# PSPS_AVNC_SRD_central-2020-10-23_FABRICA.net
KiCad netlist of a schematic drawn in EAGLE
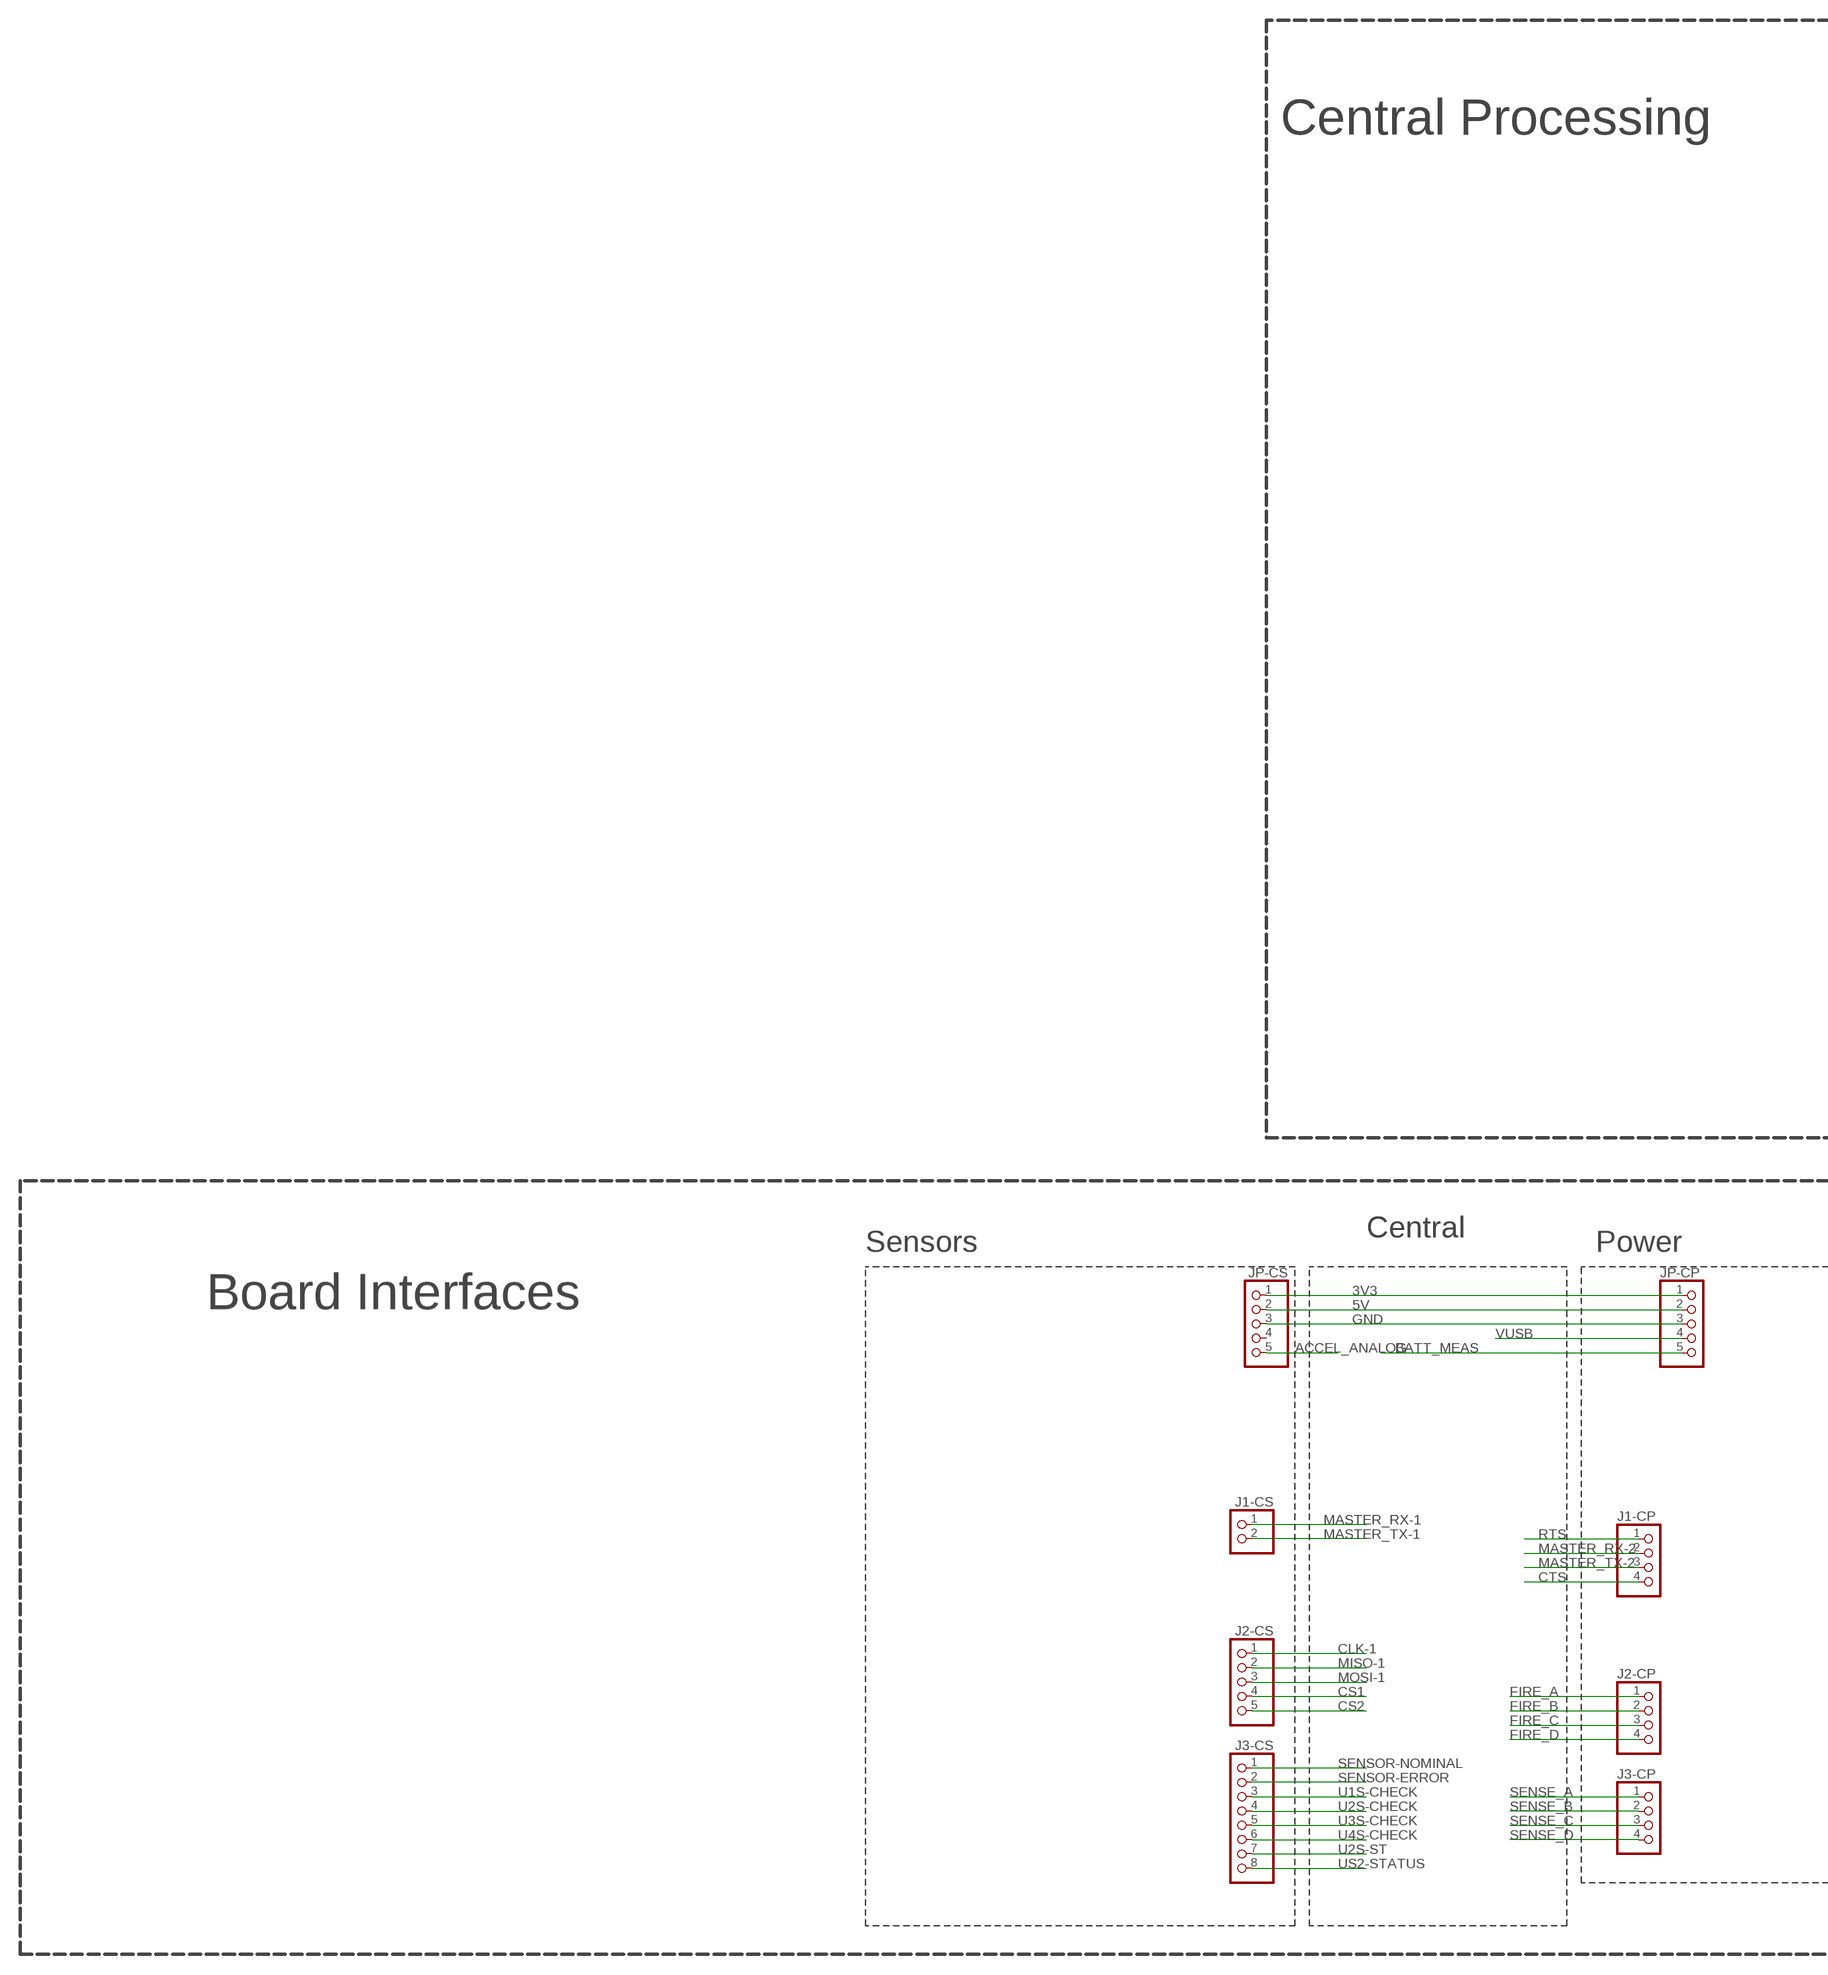
[diagram p0: schematic, sheet 1, part 1 of 2]
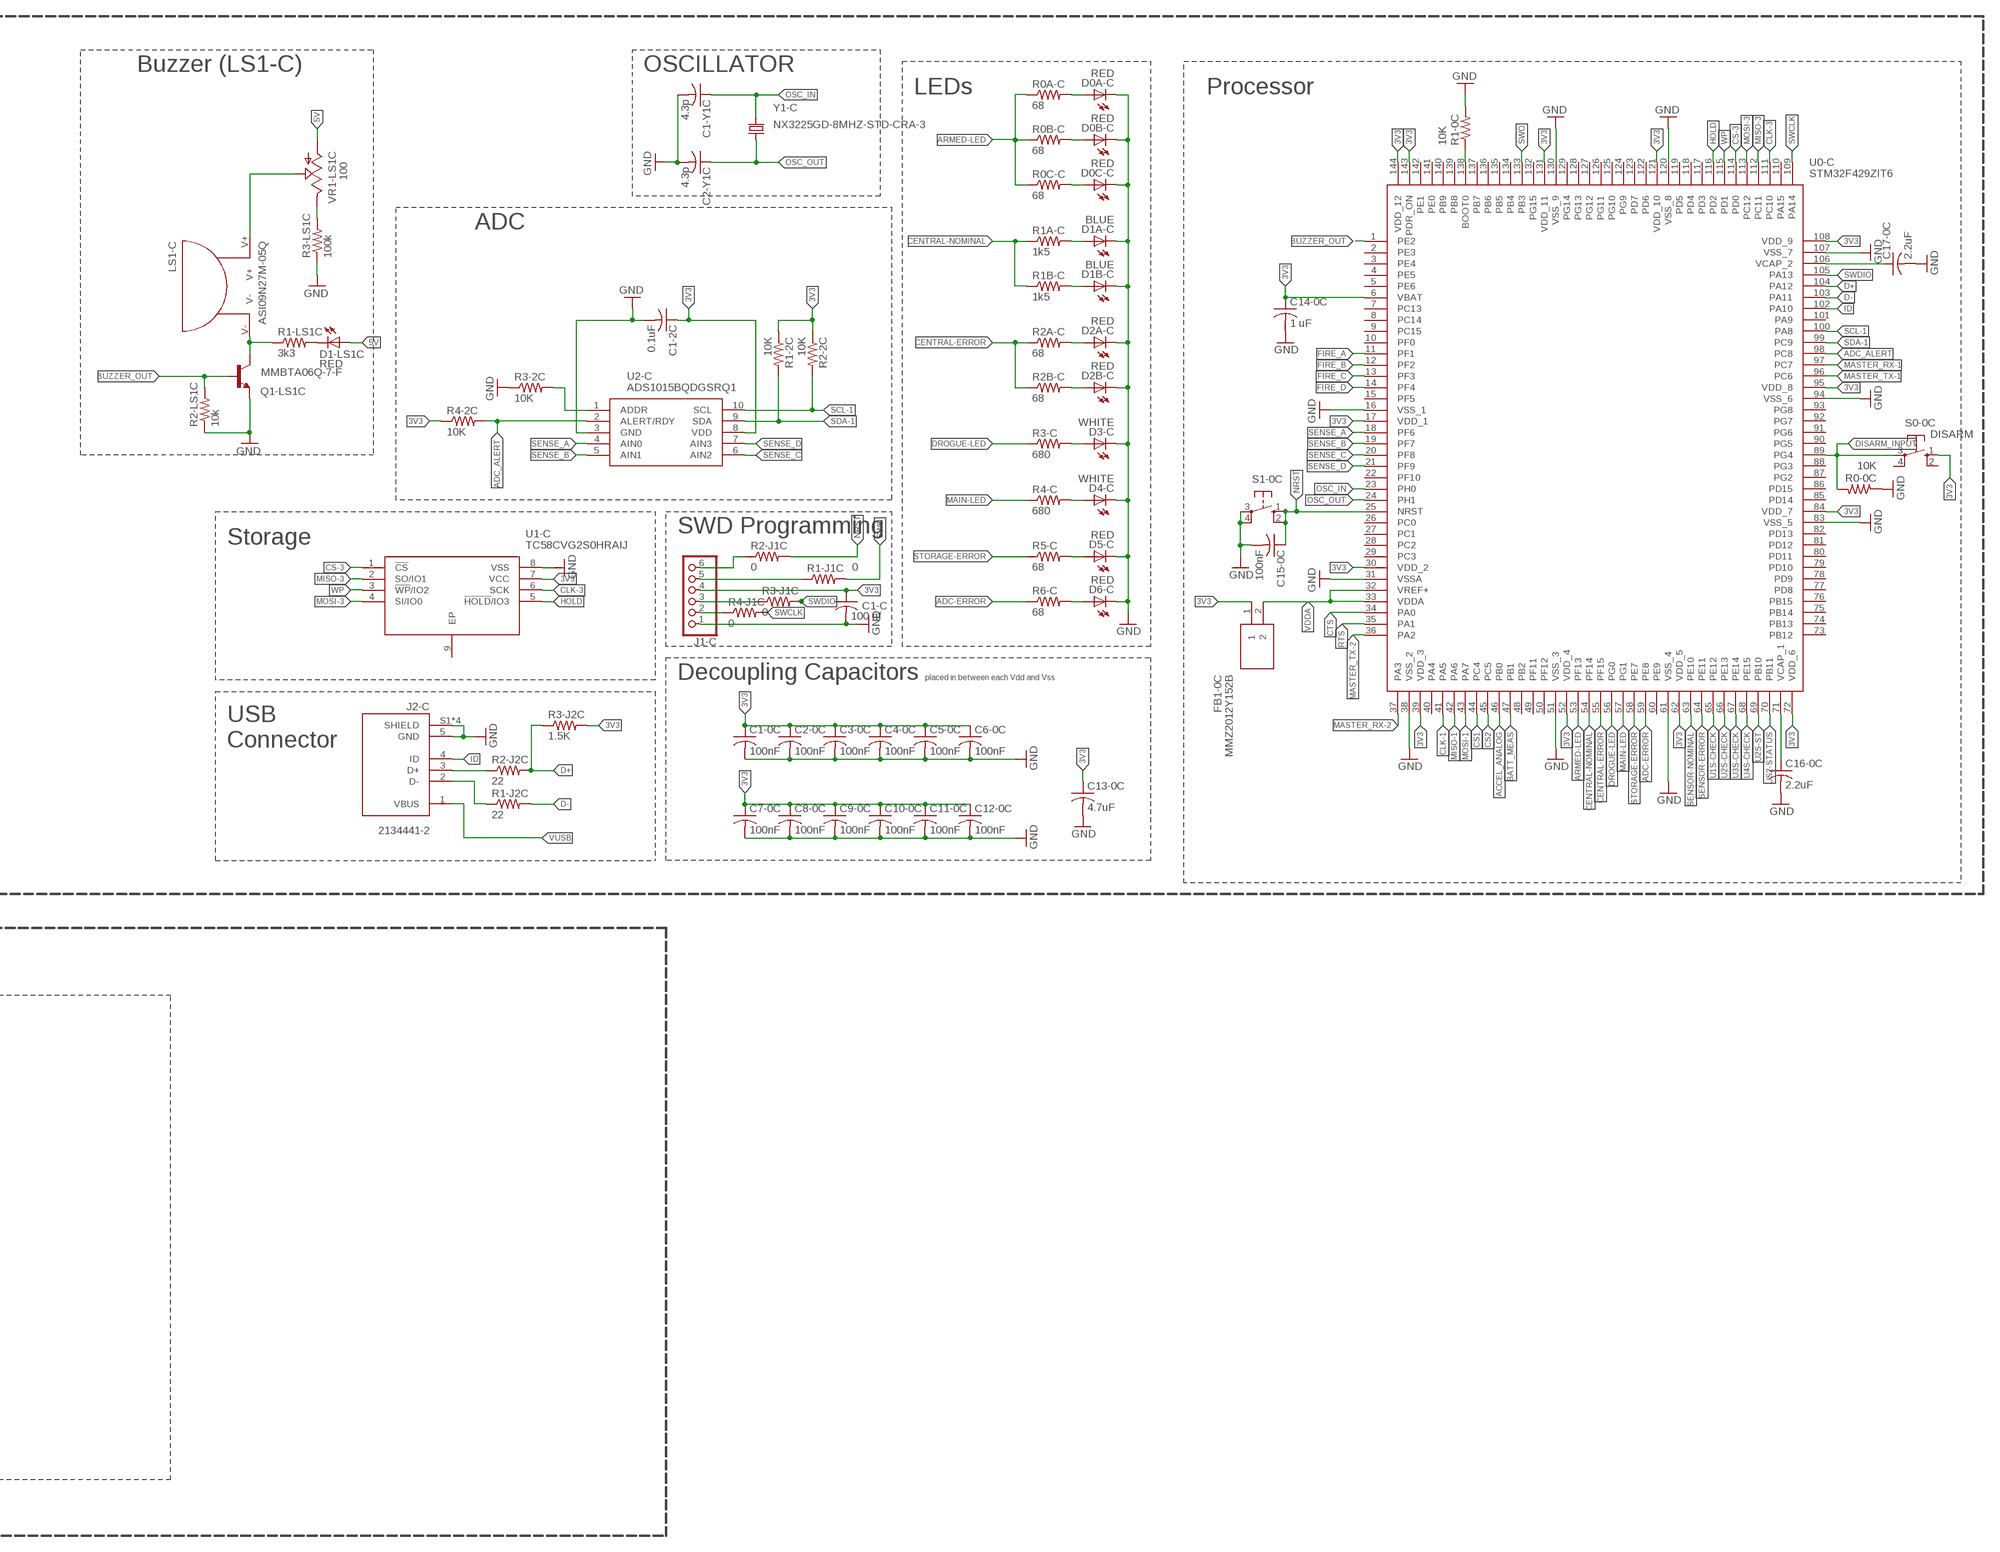
[diagram p1: schematic, sheet 1, part 2 of 2]

(export (version "E")
  (design (tool "Eeschema 10.0.6"))
  (components
    (comp (ref "C1-0C")
      (value "100nF")
      (footprint "eagle-import:C0805")
      (libsource (lib "eagle-import") (part "C-USC0805"))
    )
    (comp (ref "C1-2C")
      (value "0.1uF")
      (footprint "eagle-import:C0805")
      (libsource (lib "eagle-import") (part "C-USC0805"))
    )
    (comp (ref "C1-C")
      (value "100 nf")
      (footprint "eagle-import:C0805")
      (libsource (lib "eagle-import") (part "C-USC0805"))
    )
    (comp (ref "C1-Y1C")
      (value "4.3p")
      (footprint "eagle-import:C0805")
      (libsource (lib "eagle-import") (part "C-USC0805"))
    )
    (comp (ref "C2-0C")
      (value "100nF")
      (footprint "eagle-import:C0805")
      (libsource (lib "eagle-import") (part "C-USC0805"))
    )
    (comp (ref "C2-Y1C")
      (value "4.3p")
      (footprint "eagle-import:C0805")
      (libsource (lib "eagle-import") (part "C-USC0805"))
    )
    (comp (ref "C3-0C")
      (value "100nF")
      (footprint "eagle-import:C0805")
      (libsource (lib "eagle-import") (part "C-USC0805"))
    )
    (comp (ref "C4-0C")
      (value "100nF")
      (footprint "eagle-import:C0805")
      (libsource (lib "eagle-import") (part "C-USC0805"))
    )
    (comp (ref "C5-0C")
      (value "100nF")
      (footprint "eagle-import:C0805")
      (libsource (lib "eagle-import") (part "C-USC0805"))
    )
    (comp (ref "C6-0C")
      (value "100nF")
      (footprint "eagle-import:C0805")
      (libsource (lib "eagle-import") (part "C-USC0805"))
    )
    (comp (ref "C7-0C")
      (value "100nF")
      (footprint "eagle-import:C0805")
      (libsource (lib "eagle-import") (part "C-USC0805"))
    )
    (comp (ref "C8-0C")
      (value "100nF")
      (footprint "eagle-import:C0805")
      (libsource (lib "eagle-import") (part "C-USC0805"))
    )
    (comp (ref "C9-0C")
      (value "100nF")
      (footprint "eagle-import:C0805")
      (libsource (lib "eagle-import") (part "C-USC0805"))
    )
    (comp (ref "C10-0C")
      (value "100nF")
      (footprint "eagle-import:C0805")
      (libsource (lib "eagle-import") (part "C-USC0805"))
    )
    (comp (ref "C11-0C")
      (value "100nF")
      (footprint "eagle-import:C0805")
      (libsource (lib "eagle-import") (part "C-USC0805"))
    )
    (comp (ref "C12-0C")
      (value "100nF")
      (footprint "eagle-import:C0805")
      (libsource (lib "eagle-import") (part "C-USC0805"))
    )
    (comp (ref "C13-0C")
      (value "4.7uF")
      (footprint "eagle-import:C0805")
      (libsource (lib "eagle-import") (part "C-USC0805"))
    )
    (comp (ref "C14-0C")
      (value "1 uF")
      (footprint "eagle-import:C0805")
      (libsource (lib "eagle-import") (part "C-USC0805"))
    )
    (comp (ref "C15-0C")
      (value "100nF")
      (footprint "eagle-import:C0805")
      (libsource (lib "eagle-import") (part "C-USC0805"))
    )
    (comp (ref "C16-0C")
      (value "2.2uF")
      (footprint "eagle-import:C0805")
      (libsource (lib "eagle-import") (part "C-USC0805"))
    )
    (comp (ref "C17-0C")
      (value "2.2uF")
      (footprint "eagle-import:C0805")
      (libsource (lib "eagle-import") (part "C-USC0805"))
    )
    (comp (ref "D0A-C")
      (value "RED")
      (footprint "eagle-import:CHIPLED_0805")
      (libsource (lib "eagle-import") (part "LEDCHIPLED_0805"))
    )
    (comp (ref "D0B-C")
      (value "RED")
      (footprint "eagle-import:CHIPLED_0805")
      (libsource (lib "eagle-import") (part "LEDCHIPLED_0805"))
    )
    (comp (ref "D0C-C")
      (value "RED")
      (footprint "eagle-import:CHIPLED_0805")
      (libsource (lib "eagle-import") (part "LEDCHIPLED_0805"))
    )
    (comp (ref "D1-LS1C")
      (value "RED")
      (footprint "eagle-import:CHIPLED_0805")
      (libsource (lib "eagle-import") (part "LEDCHIPLED_0805"))
    )
    (comp (ref "D1A-C")
      (value "BLUE")
      (footprint "eagle-import:CHIPLED_0805")
      (libsource (lib "eagle-import") (part "LEDCHIPLED_0805"))
    )
    (comp (ref "D1B-C")
      (value "BLUE")
      (footprint "eagle-import:CHIPLED_0805")
      (libsource (lib "eagle-import") (part "LEDCHIPLED_0805"))
    )
    (comp (ref "D2A-C")
      (value "RED")
      (footprint "eagle-import:CHIPLED_0805")
      (libsource (lib "eagle-import") (part "LEDCHIPLED_0805"))
    )
    (comp (ref "D2B-C")
      (value "RED")
      (footprint "eagle-import:CHIPLED_0805")
      (libsource (lib "eagle-import") (part "LEDCHIPLED_0805"))
    )
    (comp (ref "D3-C")
      (value "WHITE")
      (footprint "eagle-import:CHIPLED_0805")
      (libsource (lib "eagle-import") (part "LEDCHIPLED_0805"))
    )
    (comp (ref "D4-C")
      (value "WHITE")
      (footprint "eagle-import:CHIPLED_0805")
      (libsource (lib "eagle-import") (part "LEDCHIPLED_0805"))
    )
    (comp (ref "D5-C")
      (value "RED")
      (footprint "eagle-import:CHIPLED_0805")
      (libsource (lib "eagle-import") (part "LEDCHIPLED_0805"))
    )
    (comp (ref "D6-C")
      (value "RED")
      (footprint "eagle-import:CHIPLED_0805")
      (libsource (lib "eagle-import") (part "LEDCHIPLED_0805"))
    )
    (comp (ref "FB1-0C")
      (value "MMZ2012Y152B")
      (footprint "eagle-import:BEADC2012X105N")
      (fields (field (name "MOUSER_PART_NUMBER") "810-MMZ2012Y152B"))
      (libsource (lib "eagle-import") (part "MMZ2012Y152B"))
    )
    (comp (ref "J1-C")
      (value "PINHD-1X6")
      (footprint "eagle-import:1X06")
      (libsource (lib "eagle-import") (part "PINHD-1X6"))
    )
    (comp (ref "J1-CP")
      (value "PINHD-1X4")
      (footprint "eagle-import:1X04")
      (libsource (lib "eagle-import") (part "PINHD-1X4"))
    )
    (comp (ref "J1-CS")
      (value "PINHD-1X2")
      (footprint "eagle-import:1X02")
      (libsource (lib "eagle-import") (part "PINHD-1X2"))
    )
    (comp (ref "J2-C")
      (value "2134441-2")
      (footprint "eagle-import:TE_2134441-2")
      (fields (field (name "DIGI-KEY_PART_NUMBER") "A118104CT-ND") (field (name "MF") "TE Connectivity"))
      (libsource (lib "eagle-import") (part "2134441-2"))
    )
    (comp (ref "J2-CP")
      (value "PINHD-1X4")
      (footprint "eagle-import:1X04")
      (libsource (lib "eagle-import") (part "PINHD-1X4"))
    )
    (comp (ref "J2-CS")
      (value "PINHD-1X5")
      (footprint "eagle-import:1X05")
      (libsource (lib "eagle-import") (part "PINHD-1X5"))
    )
    (comp (ref "J3-CP")
      (value "PINHD-1X4")
      (footprint "eagle-import:1X04")
      (libsource (lib "eagle-import") (part "PINHD-1X4"))
    )
    (comp (ref "J3-CS")
      (value "PINHD-1X8")
      (footprint "eagle-import:1X08")
      (libsource (lib "eagle-import") (part "PINHD-1X8"))
    )
    (comp (ref "JP-CP")
      (value "PINHD-1X5")
      (footprint "eagle-import:1X05")
      (libsource (lib "eagle-import") (part "PINHD-1X5"))
    )
    (comp (ref "JP-CS")
      (value "PINHD-1X5")
      (footprint "eagle-import:1X05")
      (libsource (lib "eagle-import") (part "PINHD-1X5"))
    )
    (comp (ref "LS1-C")
      (value "ASI09N27M-05Q")
      (footprint "eagle-import:ASI09N27M-05Q")
      (libsource (lib "eagle-import") (part "ASI09N27M-05Q"))
    )
    (comp (ref "Q1-LS1C")
      (value "MMBTA06Q-7-F")
      (footprint "eagle-import:SOT23")
      (libsource (lib "eagle-import") (part "NPN_TRANSISTOR"))
    )
    (comp (ref "R0-0C")
      (value "10K")
      (footprint "eagle-import:R0805")
      (libsource (lib "eagle-import") (part "R-US_R0805"))
    )
    (comp (ref "R0A-C")
      (value "68")
      (footprint "eagle-import:M0805")
      (libsource (lib "eagle-import") (part "R-US_M0805"))
    )
    (comp (ref "R0B-C")
      (value "68")
      (footprint "eagle-import:M0805")
      (libsource (lib "eagle-import") (part "R-US_M0805"))
    )
    (comp (ref "R0C-C")
      (value "68")
      (footprint "eagle-import:M0805")
      (libsource (lib "eagle-import") (part "R-US_M0805"))
    )
    (comp (ref "R1-0C")
      (value "10K")
      (footprint "eagle-import:R0805")
      (libsource (lib "eagle-import") (part "R-US_R0805"))
    )
    (comp (ref "R1-2C")
      (value "10K")
      (footprint "eagle-import:R0805")
      (libsource (lib "eagle-import") (part "R-US_R0805"))
    )
    (comp (ref "R1-J1C")
      (value "0")
      (footprint "eagle-import:M0805")
      (libsource (lib "eagle-import") (part "R-US_M0805"))
    )
    (comp (ref "R1-J2C")
      (value "22")
      (footprint "eagle-import:M0805")
      (libsource (lib "eagle-import") (part "R-US_M0805"))
    )
    (comp (ref "R1-LS1C")
      (value "3k3")
      (footprint "eagle-import:R0805")
      (libsource (lib "eagle-import") (part "resistor_348_R-US_R0805"))
    )
    (comp (ref "R1A-C")
      (value "1k5")
      (footprint "eagle-import:M0805")
      (libsource (lib "eagle-import") (part "R-US_M0805"))
    )
    (comp (ref "R1B-C")
      (value "1k5")
      (footprint "eagle-import:M0805")
      (libsource (lib "eagle-import") (part "R-US_M0805"))
    )
    (comp (ref "R2-2C")
      (value "10K")
      (footprint "eagle-import:R0805")
      (libsource (lib "eagle-import") (part "R-US_R0805"))
    )
    (comp (ref "R2-J1C")
      (value "0")
      (footprint "eagle-import:M0805")
      (libsource (lib "eagle-import") (part "R-US_M0805"))
    )
    (comp (ref "R2-J2C")
      (value "22")
      (footprint "eagle-import:M0805")
      (libsource (lib "eagle-import") (part "R-US_M0805"))
    )
    (comp (ref "R2-LS1C")
      (value "10k")
      (footprint "eagle-import:R0805")
      (libsource (lib "eagle-import") (part "resistor_348_R-US_R0805"))
    )
    (comp (ref "R2A-C")
      (value "68")
      (footprint "eagle-import:M0805")
      (libsource (lib "eagle-import") (part "R-US_M0805"))
    )
    (comp (ref "R2B-C")
      (value "68")
      (footprint "eagle-import:M0805")
      (libsource (lib "eagle-import") (part "R-US_M0805"))
    )
    (comp (ref "R3-2C")
      (value "10K")
      (footprint "eagle-import:R0805")
      (libsource (lib "eagle-import") (part "R-US_R0805"))
    )
    (comp (ref "R3-C")
      (value "680")
      (footprint "eagle-import:M0805")
      (libsource (lib "eagle-import") (part "R-US_M0805"))
    )
    (comp (ref "R3-J1C")
      (value "0")
      (footprint "eagle-import:M0805")
      (libsource (lib "eagle-import") (part "R-US_M0805"))
    )
    (comp (ref "R3-J2C")
      (value "1.5K")
      (footprint "eagle-import:M0805")
      (libsource (lib "eagle-import") (part "R-US_M0805"))
    )
    (comp (ref "R3-LS1C")
      (value "100k")
      (footprint "eagle-import:R0805")
      (libsource (lib "eagle-import") (part "resistor_348_R-US_R0805"))
    )
    (comp (ref "R4-2C")
      (value "10K")
      (footprint "eagle-import:R0805")
      (libsource (lib "eagle-import") (part "R-US_R0805"))
    )
    (comp (ref "R4-C")
      (value "680")
      (footprint "eagle-import:M0805")
      (libsource (lib "eagle-import") (part "R-US_M0805"))
    )
    (comp (ref "R4-J1C")
      (value "0")
      (footprint "eagle-import:M0805")
      (libsource (lib "eagle-import") (part "R-US_M0805"))
    )
    (comp (ref "R5-C")
      (value "68")
      (footprint "eagle-import:M0805")
      (libsource (lib "eagle-import") (part "R-US_M0805"))
    )
    (comp (ref "R6-C")
      (value "68")
      (footprint "eagle-import:M0805")
      (libsource (lib "eagle-import") (part "R-US_M0805"))
    )
    (comp (ref "S0-0C")
      (value "DISARM")
      (footprint "eagle-import:B3F-10XX")
      (fields (field (name "MPN") "B3F-1000"))
      (libsource (lib "eagle-import") (part "10-XX"))
    )
    (comp (ref "S1-0C")
      (value "10-XX")
      (footprint "eagle-import:B3F-10XX")
      (fields (field (name "MPN") "B3F-1000"))
      (libsource (lib "eagle-import") (part "10-XX"))
    )
    (comp (ref "U0-C")
      (value "STM32F429ZIT6")
      (footprint "eagle-import:QFP50P2200X2200X160-144N")
      (fields (field (name "MOUSER_PART_NUMBER") "511-STM32F429ZIT6"))
      (libsource (lib "eagle-import") (part "STM32F429ZIT6"))
    )
    (comp (ref "U1-C")
      (value "TC58CVG2S0HRAIJ")
      (footprint "eagle-import:SON127P800X600X80-9N")
      (fields (field (name "MOUSER_PART_NUMBER") "757-TC58CVG2S0HRAIJ"))
      (libsource (lib "eagle-import") (part "TC58CVG2S0HRAIJ"))
    )
    (comp (ref "U2-C")
      (value "ADS1015BQDGSRQ1")
      (footprint "eagle-import:SOP50P490X110-10N")
      (fields (field (name "MOUSER_PART_NUMBER") "595-ADS1015BQDGSRQ1"))
      (libsource (lib "eagle-import") (part "ADS1015BQDGSRQ1"))
    )
    (comp (ref "VR1-LS1C")
      (value "100")
      (footprint "eagle-import:LI10")
      (libsource (lib "eagle-import") (part "TRIM_US-LI10"))
    )
    (comp (ref "Y1-C")
      (value "NX3225GD-8MHZ-STD-CRA-3")
      (footprint "eagle-import:NX3225GD")
      (libsource (lib "eagle-import") (part "NX3225GD"))
    )
  )
  (nets
    (net (code "1") (name "3V3") (class "Default")
      (node (ref "C1-0C") (pin "1") (pinfunction "1_1") (pintype "passive"))
      (node (ref "C1-2C") (pin "1") (pinfunction "1_1") (pintype "passive"))
      (node (ref "C1-C") (pin "1") (pinfunction "1_1") (pintype "passive"))
      (node (ref "C10-0C") (pin "1") (pinfunction "1_1") (pintype "passive"))
      (node (ref "C11-0C") (pin "1") (pinfunction "1_1") (pintype "passive"))
      (node (ref "C12-0C") (pin "1") (pinfunction "1_1") (pintype "passive"))
      (node (ref "C13-0C") (pin "1") (pinfunction "1_1") (pintype "passive"))
      (node (ref "C14-0C") (pin "1") (pinfunction "1_1") (pintype "passive"))
      (node (ref "C2-0C") (pin "1") (pinfunction "1_1") (pintype "passive"))
      (node (ref "C3-0C") (pin "1") (pinfunction "1_1") (pintype "passive"))
      (node (ref "C4-0C") (pin "1") (pinfunction "1_1") (pintype "passive"))
      (node (ref "C5-0C") (pin "1") (pinfunction "1_1") (pintype "passive"))
      (node (ref "C6-0C") (pin "1") (pinfunction "1_1") (pintype "passive"))
      (node (ref "C7-0C") (pin "1") (pinfunction "1_1") (pintype "passive"))
      (node (ref "C8-0C") (pin "1") (pinfunction "1_1") (pintype "passive"))
      (node (ref "C9-0C") (pin "1") (pinfunction "1_1") (pintype "passive"))
      (node (ref "FB1-0C") (pin "1") (pinfunction "1_1") (pintype "bidirectional"))
      (node (ref "J1-C") (pin "4") (pinfunction "4_4") (pintype "passive"))
      (node (ref "JP-CP") (pin "1") (pinfunction "1_1") (pintype "passive"))
      (node (ref "JP-CS") (pin "1") (pinfunction "1_1") (pintype "passive"))
      (node (ref "R1-2C") (pin "1") (pinfunction "1_1") (pintype "passive"))
      (node (ref "R2-2C") (pin "1") (pinfunction "1_1") (pintype "passive"))
      (node (ref "R3-J2C") (pin "2") (pinfunction "2_2") (pintype "passive"))
      (node (ref "R4-2C") (pin "1") (pinfunction "1_1") (pintype "passive"))
      (node (ref "S0-0C") (pin "1") (pinfunction "S_1") (pintype "passive"))
      (node (ref "U0-C") (pin "108") (pinfunction "VDD_9_108") (pintype "power_in"))
      (node (ref "U0-C") (pin "121") (pinfunction "VDD_10_121") (pintype "power_in"))
      (node (ref "U0-C") (pin "131") (pinfunction "VDD_11_131") (pintype "power_in"))
      (node (ref "U0-C") (pin "143") (pinfunction "PDR_ON_143") (pintype "bidirectional"))
      (node (ref "U0-C") (pin "144") (pinfunction "VDD_12_144") (pintype "power_in"))
      (node (ref "U0-C") (pin "17") (pinfunction "VDD_1_17") (pintype "power_in"))
      (node (ref "U0-C") (pin "30") (pinfunction "VDD_2_30") (pintype "power_in"))
      (node (ref "U0-C") (pin "39") (pinfunction "VDD_3_39") (pintype "power_in"))
      (node (ref "U0-C") (pin "52") (pinfunction "VDD_4_52") (pintype "power_in"))
      (node (ref "U0-C") (pin "6") (pinfunction "VBAT_6") (pintype "bidirectional"))
      (node (ref "U0-C") (pin "62") (pinfunction "VDD_5_62") (pintype "power_in"))
      (node (ref "U0-C") (pin "72") (pinfunction "VDD_6_72") (pintype "power_in"))
      (node (ref "U0-C") (pin "84") (pinfunction "VDD_7_84") (pintype "power_in"))
      (node (ref "U0-C") (pin "95") (pinfunction "VDD_8_95") (pintype "power_in"))
      (node (ref "U1-C") (pin "7") (pinfunction "VCC_7") (pintype "bidirectional"))
      (node (ref "U2-C") (pin "8") (pinfunction "VDD_8") (pintype "bidirectional"))
    )
    (net (code "2") (name "5V") (class "Default")
      (node (ref "D1-LS1C") (pin "A") (pinfunction "A_A") (pintype "passive"))
      (node (ref "JP-CP") (pin "2") (pinfunction "2_2") (pintype "passive"))
      (node (ref "JP-CS") (pin "2") (pinfunction "2_2") (pintype "passive"))
      (node (ref "VR1-LS1C") (pin "A") (pinfunction "A_A") (pintype "passive"))
    )
    (net (code "3") (name "ACCEL_ANALOG") (class "Default")
      (node (ref "JP-CS") (pin "5") (pinfunction "5_5") (pintype "passive"))
      (node (ref "U0-C") (pin "46") (pinfunction "PB0_46") (pintype "bidirectional"))
    )
    (net (code "4") (name "ADC-ERROR") (class "Default")
      (node (ref "R6-C") (pin "1") (pinfunction "1_1") (pintype "passive"))
      (node (ref "U0-C") (pin "59") (pinfunction "PE8_59") (pintype "bidirectional"))
    )
    (net (code "5") (name "ADC_ALERT") (class "Default")
      (node (ref "R4-2C") (pin "2") (pinfunction "2_2") (pintype "passive"))
      (node (ref "U0-C") (pin "98") (pinfunction "PC8_98") (pintype "bidirectional"))
      (node (ref "U2-C") (pin "2") (pinfunction "ALERT/RDY_2") (pintype "bidirectional"))
    )
    (net (code "6") (name "ARMED-LED") (class "Default")
      (node (ref "R0A-C") (pin "1") (pinfunction "1_1") (pintype "passive"))
      (node (ref "R0B-C") (pin "1") (pinfunction "1_1") (pintype "passive"))
      (node (ref "R0C-C") (pin "1") (pinfunction "1_1") (pintype "passive"))
      (node (ref "U0-C") (pin "53") (pinfunction "PF13_53") (pintype "bidirectional"))
    )
    (net (code "7") (name "BATT_MEAS") (class "Default")
      (node (ref "JP-CP") (pin "5") (pinfunction "5_5") (pintype "passive"))
      (node (ref "U0-C") (pin "47") (pinfunction "PB1_47") (pintype "bidirectional"))
    )
    (net (code "8") (name "BUZZER_OUT") (class "Default")
      (node (ref "Q1-LS1C") (pin "1") (pinfunction "B_1") (pintype "passive"))
      (node (ref "R2-LS1C") (pin "2") (pinfunction "2_2") (pintype "passive"))
      (node (ref "U0-C") (pin "1") (pinfunction "PE2_1") (pintype "bidirectional"))
    )
    (net (code "9") (name "CENTRAL-ERROR") (class "Default")
      (node (ref "R2A-C") (pin "1") (pinfunction "1_1") (pintype "passive"))
      (node (ref "R2B-C") (pin "1") (pinfunction "1_1") (pintype "passive"))
      (node (ref "U0-C") (pin "55") (pinfunction "PF15_55") (pintype "bidirectional"))
    )
    (net (code "10") (name "CENTRAL-NOMINAL") (class "Default")
      (node (ref "R1A-C") (pin "1") (pinfunction "1_1") (pintype "passive"))
      (node (ref "R1B-C") (pin "1") (pinfunction "1_1") (pintype "passive"))
      (node (ref "U0-C") (pin "54") (pinfunction "PF14_54") (pintype "bidirectional"))
    )
    (net (code "11") (name "CLK-1") (class "Default")
      (node (ref "J2-CS") (pin "1") (pinfunction "1_1") (pintype "passive"))
      (node (ref "U0-C") (pin "41") (pinfunction "PA5_41") (pintype "bidirectional"))
    )
    (net (code "12") (name "CLK-3") (class "Default")
      (node (ref "U0-C") (pin "111") (pinfunction "PC10_111") (pintype "bidirectional"))
      (node (ref "U1-C") (pin "6") (pinfunction "SCK_6") (pintype "bidirectional"))
    )
    (net (code "13") (name "CS-3") (class "Default")
      (node (ref "U0-C") (pin "114") (pinfunction "PD0_114") (pintype "bidirectional"))
      (node (ref "U1-C") (pin "1") (pinfunction "~{CS}_1") (pintype "bidirectional"))
    )
    (net (code "14") (name "CS1") (class "Default")
      (node (ref "J2-CS") (pin "4") (pinfunction "4_4") (pintype "passive"))
      (node (ref "U0-C") (pin "44") (pinfunction "PC4_44") (pintype "bidirectional"))
    )
    (net (code "15") (name "CS2") (class "Default")
      (node (ref "J2-CS") (pin "5") (pinfunction "5_5") (pintype "passive"))
      (node (ref "U0-C") (pin "45") (pinfunction "PC5_45") (pintype "bidirectional"))
    )
    (net (code "16") (name "CTS") (class "Default")
      (node (ref "J1-CP") (pin "4") (pinfunction "4_4") (pintype "passive"))
      (node (ref "U0-C") (pin "34") (pinfunction "PA0_34") (pintype "bidirectional"))
    )
    (net (code "17") (name "D+") (class "Default")
      (node (ref "R2-J2C") (pin "2") (pinfunction "2_2") (pintype "passive"))
      (node (ref "R3-J2C") (pin "1") (pinfunction "1_1") (pintype "passive"))
      (node (ref "U0-C") (pin "104") (pinfunction "PA12_104") (pintype "bidirectional"))
    )
    (net (code "18") (name "D-") (class "Default")
      (node (ref "R1-J2C") (pin "2") (pinfunction "2_2") (pintype "passive"))
      (node (ref "U0-C") (pin "103") (pinfunction "PA11_103") (pintype "bidirectional"))
    )
    (net (code "19") (name "DISARM_INPUT") (class "Default")
      (node (ref "R0-0C") (pin "2") (pinfunction "2_2") (pintype "passive"))
      (node (ref "S0-0C") (pin "3") (pinfunction "P_3") (pintype "passive"))
      (node (ref "U0-C") (pin "89") (pinfunction "PG4_89") (pintype "bidirectional"))
    )
    (net (code "20") (name "DROGUE-LED") (class "Default")
      (node (ref "R3-C") (pin "1") (pinfunction "1_1") (pintype "passive"))
      (node (ref "U0-C") (pin "56") (pinfunction "PG0_56") (pintype "bidirectional"))
    )
    (net (code "21") (name "FIRE_A") (class "Default")
      (node (ref "J2-CP") (pin "1") (pinfunction "1_1") (pintype "passive"))
      (node (ref "U0-C") (pin "11") (pinfunction "PF1_11") (pintype "bidirectional"))
    )
    (net (code "22") (name "FIRE_B") (class "Default")
      (node (ref "J2-CP") (pin "2") (pinfunction "2_2") (pintype "passive"))
      (node (ref "U0-C") (pin "12") (pinfunction "PF2_12") (pintype "bidirectional"))
    )
    (net (code "23") (name "FIRE_C") (class "Default")
      (node (ref "J2-CP") (pin "3") (pinfunction "3_3") (pintype "passive"))
      (node (ref "U0-C") (pin "13") (pinfunction "PF3_13") (pintype "bidirectional"))
    )
    (net (code "24") (name "FIRE_D") (class "Default")
      (node (ref "J2-CP") (pin "4") (pinfunction "4_4") (pintype "passive"))
      (node (ref "U0-C") (pin "14") (pinfunction "PF4_14") (pintype "bidirectional"))
    )
    (net (code "25") (name "GND") (class "Default")
      (node (ref "C1-0C") (pin "2") (pinfunction "2_2") (pintype "passive"))
      (node (ref "C1-2C") (pin "2") (pinfunction "2_2") (pintype "passive"))
      (node (ref "C1-C") (pin "2") (pinfunction "2_2") (pintype "passive"))
      (node (ref "C1-Y1C") (pin "2") (pinfunction "2_2") (pintype "passive"))
      (node (ref "C10-0C") (pin "2") (pinfunction "2_2") (pintype "passive"))
      (node (ref "C11-0C") (pin "2") (pinfunction "2_2") (pintype "passive"))
      (node (ref "C12-0C") (pin "2") (pinfunction "2_2") (pintype "passive"))
      (node (ref "C13-0C") (pin "2") (pinfunction "2_2") (pintype "passive"))
      (node (ref "C14-0C") (pin "2") (pinfunction "2_2") (pintype "passive"))
      (node (ref "C15-0C") (pin "2") (pinfunction "2_2") (pintype "passive"))
      (node (ref "C16-0C") (pin "2") (pinfunction "2_2") (pintype "passive"))
      (node (ref "C17-0C") (pin "2") (pinfunction "2_2") (pintype "passive"))
      (node (ref "C2-0C") (pin "2") (pinfunction "2_2") (pintype "passive"))
      (node (ref "C2-Y1C") (pin "2") (pinfunction "2_2") (pintype "passive"))
      (node (ref "C3-0C") (pin "2") (pinfunction "2_2") (pintype "passive"))
      (node (ref "C4-0C") (pin "2") (pinfunction "2_2") (pintype "passive"))
      (node (ref "C5-0C") (pin "2") (pinfunction "2_2") (pintype "passive"))
      (node (ref "C6-0C") (pin "2") (pinfunction "2_2") (pintype "passive"))
      (node (ref "C7-0C") (pin "2") (pinfunction "2_2") (pintype "passive"))
      (node (ref "C8-0C") (pin "2") (pinfunction "2_2") (pintype "passive"))
      (node (ref "C9-0C") (pin "2") (pinfunction "2_2") (pintype "passive"))
      (node (ref "D0A-C") (pin "C") (pinfunction "C_C") (pintype "passive"))
      (node (ref "D0B-C") (pin "C") (pinfunction "C_C") (pintype "passive"))
      (node (ref "D0C-C") (pin "C") (pinfunction "C_C") (pintype "passive"))
      (node (ref "D1A-C") (pin "C") (pinfunction "C_C") (pintype "passive"))
      (node (ref "D1B-C") (pin "C") (pinfunction "C_C") (pintype "passive"))
      (node (ref "D2A-C") (pin "C") (pinfunction "C_C") (pintype "passive"))
      (node (ref "D2B-C") (pin "C") (pinfunction "C_C") (pintype "passive"))
      (node (ref "D3-C") (pin "C") (pinfunction "C_C") (pintype "passive"))
      (node (ref "D4-C") (pin "C") (pinfunction "C_C") (pintype "passive"))
      (node (ref "D5-C") (pin "C") (pinfunction "C_C") (pintype "passive"))
      (node (ref "D6-C") (pin "C") (pinfunction "C_C") (pintype "passive"))
      (node (ref "J1-C") (pin "1") (pinfunction "1_1") (pintype "passive"))
      (node (ref "J2-C") (pin "5") (pinfunction "GND_5") (pintype "power_in"))
      (node (ref "J2-C") (pin "S1") (pinfunction "SHIELD_S1") (pintype "power_in"))
      (node (ref "J2-C") (pin "S2") (pinfunction "SHIELD_S2") (pintype "power_in"))
      (node (ref "J2-C") (pin "S3") (pinfunction "SHIELD_S3") (pintype "power_in"))
      (node (ref "J2-C") (pin "S4") (pinfunction "SHIELD_S4") (pintype "power_in"))
      (node (ref "JP-CP") (pin "3") (pinfunction "3_3") (pintype "passive"))
      (node (ref "JP-CS") (pin "3") (pinfunction "3_3") (pintype "passive"))
      (node (ref "Q1-LS1C") (pin "3") (pinfunction "E_3") (pintype "passive"))
      (node (ref "R0-0C") (pin "1") (pinfunction "1_1") (pintype "passive"))
      (node (ref "R1-0C") (pin "2") (pinfunction "2_2") (pintype "passive"))
      (node (ref "R2-LS1C") (pin "1") (pinfunction "1_1") (pintype "passive"))
      (node (ref "R3-2C") (pin "1") (pinfunction "1_1") (pintype "passive"))
      (node (ref "R3-LS1C") (pin "1") (pinfunction "1_1") (pintype "passive"))
      (node (ref "S1-0C") (pin "3") (pinfunction "P_3") (pintype "passive"))
      (node (ref "S1-0C") (pin "4") (pinfunction "P1_4") (pintype "passive"))
      (node (ref "U0-C") (pin "107") (pinfunction "VSS_7_107") (pintype "power_in"))
      (node (ref "U0-C") (pin "120") (pinfunction "VSS_8_120") (pintype "power_in"))
      (node (ref "U0-C") (pin "130") (pinfunction "VSS_9_130") (pintype "power_in"))
      (node (ref "U0-C") (pin "16") (pinfunction "VSS_1_16") (pintype "power_in"))
      (node (ref "U0-C") (pin "31") (pinfunction "VSSA_31") (pintype "power_in"))
      (node (ref "U0-C") (pin "38") (pinfunction "VSS_2_38") (pintype "power_in"))
      (node (ref "U0-C") (pin "51") (pinfunction "VSS_3_51") (pintype "power_in"))
      (node (ref "U0-C") (pin "61") (pinfunction "VSS_4_61") (pintype "power_in"))
      (node (ref "U0-C") (pin "83") (pinfunction "VSS_5_83") (pintype "power_in"))
      (node (ref "U0-C") (pin "94") (pinfunction "VSS_6_94") (pintype "power_in"))
      (node (ref "U1-C") (pin "8") (pinfunction "VSS_8") (pintype "bidirectional"))
      (node (ref "U2-C") (pin "3") (pinfunction "GND_3") (pintype "bidirectional"))
    )
    (net (code "26") (name "HOLD") (class "Default")
      (node (ref "U0-C") (pin "116") (pinfunction "PD2_116") (pintype "bidirectional"))
      (node (ref "U1-C") (pin "5") (pinfunction "~{HOLD}/IO3_5") (pintype "bidirectional"))
    )
    (net (code "27") (name "ID") (class "Default")
      (node (ref "J2-C") (pin "4") (pinfunction "ID_4") (pintype "bidirectional"))
      (node (ref "U0-C") (pin "102") (pinfunction "PA10_102") (pintype "bidirectional"))
    )
    (net (code "28") (name "MAIN-LED") (class "Default")
      (node (ref "R4-C") (pin "1") (pinfunction "1_1") (pintype "passive"))
      (node (ref "U0-C") (pin "57") (pinfunction "PG1_57") (pintype "bidirectional"))
    )
    (net (code "29") (name "MASTER_RX-1") (class "Default")
      (node (ref "J1-CS") (pin "1") (pinfunction "1_1") (pintype "passive"))
      (node (ref "U0-C") (pin "97") (pinfunction "PC7_97") (pintype "bidirectional"))
    )
    (net (code "30") (name "MASTER_RX-2") (class "Default")
      (node (ref "J1-CP") (pin "2") (pinfunction "2_2") (pintype "passive"))
      (node (ref "U0-C") (pin "37") (pinfunction "PA3_37") (pintype "bidirectional"))
    )
    (net (code "31") (name "MASTER_TX-1") (class "Default")
      (node (ref "J1-CS") (pin "2") (pinfunction "2_2") (pintype "passive"))
      (node (ref "U0-C") (pin "96") (pinfunction "PC6_96") (pintype "bidirectional"))
    )
    (net (code "32") (name "MASTER_TX-2") (class "Default")
      (node (ref "J1-CP") (pin "3") (pinfunction "3_3") (pintype "passive"))
      (node (ref "U0-C") (pin "36") (pinfunction "PA2_36") (pintype "bidirectional"))
    )
    (net (code "33") (name "MISO-1") (class "Default")
      (node (ref "J2-CS") (pin "2") (pinfunction "2_2") (pintype "passive"))
      (node (ref "U0-C") (pin "42") (pinfunction "PA6_42") (pintype "bidirectional"))
    )
    (net (code "34") (name "MISO-3") (class "Default")
      (node (ref "U0-C") (pin "112") (pinfunction "PC11_112") (pintype "bidirectional"))
      (node (ref "U1-C") (pin "2") (pinfunction "SO/IO1_2") (pintype "bidirectional"))
    )
    (net (code "35") (name "MOSI-1") (class "Default")
      (node (ref "J2-CS") (pin "3") (pinfunction "3_3") (pintype "passive"))
      (node (ref "U0-C") (pin "43") (pinfunction "PA7_43") (pintype "bidirectional"))
    )
    (net (code "36") (name "MOSI-3") (class "Default")
      (node (ref "U0-C") (pin "113") (pinfunction "PC12_113") (pintype "bidirectional"))
      (node (ref "U1-C") (pin "4") (pinfunction "SI/IO0_4") (pintype "bidirectional"))
    )
    (net (code "37") (name "NRST") (class "Default")
      (node (ref "C15-0C") (pin "1") (pinfunction "1_1") (pintype "passive"))
      (node (ref "R2-J1C") (pin "2") (pinfunction "2_2") (pintype "passive"))
      (node (ref "S1-0C") (pin "1") (pinfunction "S_1") (pintype "passive"))
      (node (ref "S1-0C") (pin "2") (pinfunction "S1_2") (pintype "passive"))
      (node (ref "U0-C") (pin "25") (pinfunction "NRST_25") (pintype "input"))
    )
    (net (code "38") (name "Net-(D0A-C-PadA)") (class "Default")
      (node (ref "D0A-C") (pin "A") (pinfunction "A_A") (pintype "passive"))
      (node (ref "R0A-C") (pin "2") (pinfunction "2_2") (pintype "passive"))
    )
    (net (code "39") (name "Net-(D0B-C-PadA)") (class "Default")
      (node (ref "D0B-C") (pin "A") (pinfunction "A_A") (pintype "passive"))
      (node (ref "R0B-C") (pin "2") (pinfunction "2_2") (pintype "passive"))
    )
    (net (code "40") (name "Net-(D0C-C-PadA)") (class "Default")
      (node (ref "D0C-C") (pin "A") (pinfunction "A_A") (pintype "passive"))
      (node (ref "R0C-C") (pin "2") (pinfunction "2_2") (pintype "passive"))
    )
    (net (code "41") (name "Net-(D1-LS1C-PadC)") (class "Default")
      (node (ref "D1-LS1C") (pin "C") (pinfunction "C_C") (pintype "passive"))
      (node (ref "R1-LS1C") (pin "2") (pinfunction "2_2") (pintype "passive"))
    )
    (net (code "42") (name "Net-(D1A-C-PadA)") (class "Default")
      (node (ref "D1A-C") (pin "A") (pinfunction "A_A") (pintype "passive"))
      (node (ref "R1A-C") (pin "2") (pinfunction "2_2") (pintype "passive"))
    )
    (net (code "43") (name "Net-(D1B-C-PadA)") (class "Default")
      (node (ref "D1B-C") (pin "A") (pinfunction "A_A") (pintype "passive"))
      (node (ref "R1B-C") (pin "2") (pinfunction "2_2") (pintype "passive"))
    )
    (net (code "44") (name "Net-(D2A-C-PadA)") (class "Default")
      (node (ref "D2A-C") (pin "A") (pinfunction "A_A") (pintype "passive"))
      (node (ref "R2A-C") (pin "2") (pinfunction "2_2") (pintype "passive"))
    )
    (net (code "45") (name "Net-(D2B-C-PadA)") (class "Default")
      (node (ref "D2B-C") (pin "A") (pinfunction "A_A") (pintype "passive"))
      (node (ref "R2B-C") (pin "2") (pinfunction "2_2") (pintype "passive"))
    )
    (net (code "46") (name "Net-(D3-C-PadA)") (class "Default")
      (node (ref "D3-C") (pin "A") (pinfunction "A_A") (pintype "passive"))
      (node (ref "R3-C") (pin "2") (pinfunction "2_2") (pintype "passive"))
    )
    (net (code "47") (name "Net-(D4-C-PadA)") (class "Default")
      (node (ref "D4-C") (pin "A") (pinfunction "A_A") (pintype "passive"))
      (node (ref "R4-C") (pin "2") (pinfunction "2_2") (pintype "passive"))
    )
    (net (code "48") (name "Net-(D5-C-PadA)") (class "Default")
      (node (ref "D5-C") (pin "A") (pinfunction "A_A") (pintype "passive"))
      (node (ref "R5-C") (pin "2") (pinfunction "2_2") (pintype "passive"))
    )
    (net (code "49") (name "Net-(D6-C-PadA)") (class "Default")
      (node (ref "D6-C") (pin "A") (pinfunction "A_A") (pintype "passive"))
      (node (ref "R6-C") (pin "2") (pinfunction "2_2") (pintype "passive"))
    )
    (net (code "50") (name "Net-(J1-C-Pad2)") (class "Default")
      (node (ref "J1-C") (pin "2") (pinfunction "2_2") (pintype "passive"))
      (node (ref "R4-J1C") (pin "1") (pinfunction "1_1") (pintype "passive"))
    )
    (net (code "51") (name "Net-(J1-C-Pad3)") (class "Default")
      (node (ref "J1-C") (pin "3") (pinfunction "3_3") (pintype "passive"))
      (node (ref "R3-J1C") (pin "1") (pinfunction "1_1") (pintype "passive"))
    )
    (net (code "52") (name "Net-(J1-C-Pad5)") (class "Default")
      (node (ref "J1-C") (pin "5") (pinfunction "5_5") (pintype "passive"))
      (node (ref "R1-J1C") (pin "1") (pinfunction "1_1") (pintype "passive"))
    )
    (net (code "53") (name "Net-(J1-C-Pad6)") (class "Default")
      (node (ref "J1-C") (pin "6") (pinfunction "6_6") (pintype "passive"))
      (node (ref "R2-J1C") (pin "1") (pinfunction "1_1") (pintype "passive"))
    )
    (net (code "54") (name "Net-(J2-C-D+)") (class "Default")
      (node (ref "J2-C") (pin "3") (pinfunction "D+_3") (pintype "bidirectional"))
      (node (ref "R2-J2C") (pin "1") (pinfunction "1_1") (pintype "passive"))
    )
    (net (code "55") (name "Net-(J2-C-D-)") (class "Default")
      (node (ref "J2-C") (pin "2") (pinfunction "D-_2") (pintype "bidirectional"))
      (node (ref "R1-J2C") (pin "1") (pinfunction "1_1") (pintype "passive"))
    )
    (net (code "56") (name "Net-(LS1-C-PadV+)") (class "Default")
      (node (ref "LS1-C") (pin "V+") (pinfunction "V+_V+") (pintype "bidirectional"))
      (node (ref "VR1-LS1C") (pin "S") (pinfunction "S_S") (pintype "passive"))
    )
    (net (code "57") (name "Net-(Q1-LS1C-C)") (class "Default")
      (node (ref "LS1-C") (pin "V-") (pinfunction "V-_V-") (pintype "bidirectional"))
      (node (ref "Q1-LS1C") (pin "2") (pinfunction "C_2") (pintype "passive"))
      (node (ref "R1-LS1C") (pin "1") (pinfunction "1_1") (pintype "passive"))
    )
    (net (code "58") (name "Net-(R3-LS1C-Pad2)") (class "Default")
      (node (ref "R3-LS1C") (pin "2") (pinfunction "2_2") (pintype "passive"))
      (node (ref "VR1-LS1C") (pin "E") (pinfunction "E_E") (pintype "passive"))
    )
    (net (code "59") (name "Net-(U0-C-BOOT0)") (class "Default")
      (node (ref "R1-0C") (pin "1") (pinfunction "1_1") (pintype "passive"))
      (node (ref "U0-C") (pin "138") (pinfunction "BOOT0_138") (pintype "bidirectional"))
    )
    (net (code "60") (name "Net-(U0-C-VCAP_1)") (class "Default")
      (node (ref "C16-0C") (pin "1") (pinfunction "1_1") (pintype "passive"))
      (node (ref "U0-C") (pin "71") (pinfunction "VCAP_1_71") (pintype "bidirectional"))
    )
    (net (code "61") (name "Net-(U0-C-VCAP_2)") (class "Default")
      (node (ref "C17-0C") (pin "1") (pinfunction "1_1") (pintype "passive"))
      (node (ref "U0-C") (pin "106") (pinfunction "VCAP_2_106") (pintype "bidirectional"))
    )
    (net (code "62") (name "Net-(U2-C-ADDR)") (class "Default")
      (node (ref "R3-2C") (pin "2") (pinfunction "2_2") (pintype "passive"))
      (node (ref "U2-C") (pin "1") (pinfunction "ADDR_1") (pintype "bidirectional"))
    )
    (net (code "63") (name "OSC_IN") (class "Default")
      (node (ref "C1-Y1C") (pin "1") (pinfunction "1_1") (pintype "passive"))
      (node (ref "U0-C") (pin "23") (pinfunction "PH0_23") (pintype "bidirectional"))
      (node (ref "Y1-C") (pin "P$2") (pinfunction "2_P$2") (pintype "passive"))
    )
    (net (code "64") (name "OSC_OUT") (class "Default")
      (node (ref "C2-Y1C") (pin "1") (pinfunction "1_1") (pintype "passive"))
      (node (ref "U0-C") (pin "24") (pinfunction "PH1_24") (pintype "bidirectional"))
      (node (ref "Y1-C") (pin "P$1") (pinfunction "1_P$1") (pintype "passive"))
    )
    (net (code "65") (name "RTS") (class "Default")
      (node (ref "J1-CP") (pin "1") (pinfunction "1_1") (pintype "passive"))
      (node (ref "U0-C") (pin "35") (pinfunction "PA1_35") (pintype "bidirectional"))
    )
    (net (code "66") (name "SCL-1") (class "Default")
      (node (ref "R2-2C") (pin "2") (pinfunction "2_2") (pintype "passive"))
      (node (ref "U0-C") (pin "100") (pinfunction "PA8_100") (pintype "bidirectional"))
      (node (ref "U2-C") (pin "10") (pinfunction "SCL_10") (pintype "bidirectional"))
    )
    (net (code "67") (name "SDA-1") (class "Default")
      (node (ref "R1-2C") (pin "2") (pinfunction "2_2") (pintype "passive"))
      (node (ref "U0-C") (pin "99") (pinfunction "PC9_99") (pintype "bidirectional"))
      (node (ref "U2-C") (pin "9") (pinfunction "SDA_9") (pintype "bidirectional"))
    )
    (net (code "68") (name "SENSE_A") (class "Default")
      (node (ref "J3-CP") (pin "1") (pinfunction "1_1") (pintype "passive"))
      (node (ref "U0-C") (pin "18") (pinfunction "PF6_18") (pintype "bidirectional"))
      (node (ref "U2-C") (pin "4") (pinfunction "AIN0_4") (pintype "bidirectional"))
    )
    (net (code "69") (name "SENSE_B") (class "Default")
      (node (ref "J3-CP") (pin "2") (pinfunction "2_2") (pintype "passive"))
      (node (ref "U0-C") (pin "19") (pinfunction "PF7_19") (pintype "bidirectional"))
      (node (ref "U2-C") (pin "5") (pinfunction "AIN1_5") (pintype "bidirectional"))
    )
    (net (code "70") (name "SENSE_C") (class "Default")
      (node (ref "J3-CP") (pin "3") (pinfunction "3_3") (pintype "passive"))
      (node (ref "U0-C") (pin "20") (pinfunction "PF8_20") (pintype "bidirectional"))
      (node (ref "U2-C") (pin "6") (pinfunction "AIN2_6") (pintype "bidirectional"))
    )
    (net (code "71") (name "SENSE_D") (class "Default")
      (node (ref "J3-CP") (pin "4") (pinfunction "4_4") (pintype "passive"))
      (node (ref "U0-C") (pin "21") (pinfunction "PF9_21") (pintype "bidirectional"))
      (node (ref "U2-C") (pin "7") (pinfunction "AIN3_7") (pintype "bidirectional"))
    )
    (net (code "72") (name "SENSOR-ERROR") (class "Default")
      (node (ref "J3-CS") (pin "2") (pinfunction "2_2") (pintype "passive"))
      (node (ref "U0-C") (pin "64") (pinfunction "PE11_64") (pintype "bidirectional"))
    )
    (net (code "73") (name "SENSOR-NOMINAL") (class "Default")
      (node (ref "J3-CS") (pin "1") (pinfunction "1_1") (pintype "passive"))
      (node (ref "U0-C") (pin "63") (pinfunction "PE10_63") (pintype "bidirectional"))
    )
    (net (code "74") (name "STORAGE-ERROR") (class "Default")
      (node (ref "R5-C") (pin "1") (pinfunction "1_1") (pintype "passive"))
      (node (ref "U0-C") (pin "58") (pinfunction "PE7_58") (pintype "bidirectional"))
    )
    (net (code "75") (name "SWCLK") (class "Default")
      (node (ref "R4-J1C") (pin "2") (pinfunction "2_2") (pintype "passive"))
      (node (ref "U0-C") (pin "109") (pinfunction "PA14_109") (pintype "bidirectional"))
    )
    (net (code "76") (name "SWDIO") (class "Default")
      (node (ref "R3-J1C") (pin "2") (pinfunction "2_2") (pintype "passive"))
      (node (ref "U0-C") (pin "105") (pinfunction "PA13_105") (pintype "bidirectional"))
    )
    (net (code "77") (name "SWO") (class "Default")
      (node (ref "R1-J1C") (pin "2") (pinfunction "2_2") (pintype "passive"))
      (node (ref "U0-C") (pin "133") (pinfunction "PB3_133") (pintype "bidirectional"))
    )
    (net (code "78") (name "U1S-CHECK") (class "Default")
      (node (ref "J3-CS") (pin "3") (pinfunction "3_3") (pintype "passive"))
      (node (ref "U0-C") (pin "65") (pinfunction "PE12_65") (pintype "bidirectional"))
    )
    (net (code "79") (name "U2S-CHECK") (class "Default")
      (node (ref "J3-CS") (pin "4") (pinfunction "4_4") (pintype "passive"))
      (node (ref "U0-C") (pin "66") (pinfunction "PE13_66") (pintype "bidirectional"))
    )
    (net (code "80") (name "U2S-ST") (class "Default")
      (node (ref "J3-CS") (pin "7") (pinfunction "7_7") (pintype "passive"))
      (node (ref "U0-C") (pin "69") (pinfunction "PB10_69") (pintype "bidirectional"))
    )
    (net (code "81") (name "U3S-CHECK") (class "Default")
      (node (ref "J3-CS") (pin "5") (pinfunction "5_5") (pintype "passive"))
      (node (ref "U0-C") (pin "67") (pinfunction "PE14_67") (pintype "bidirectional"))
    )
    (net (code "82") (name "U4S-CHECK") (class "Default")
      (node (ref "J3-CS") (pin "6") (pinfunction "6_6") (pintype "passive"))
      (node (ref "U0-C") (pin "68") (pinfunction "PE15_68") (pintype "bidirectional"))
    )
    (net (code "83") (name "US2-STATUS") (class "Default")
      (node (ref "J3-CS") (pin "8") (pinfunction "8_8") (pintype "passive"))
      (node (ref "U0-C") (pin "70") (pinfunction "PB11_70") (pintype "bidirectional"))
    )
    (net (code "84") (name "VDDA") (class "Default")
      (node (ref "FB1-0C") (pin "2") (pinfunction "2_2") (pintype "bidirectional"))
      (node (ref "U0-C") (pin "32") (pinfunction "VREF+_32") (pintype "input"))
      (node (ref "U0-C") (pin "33") (pinfunction "VDDA_33") (pintype "power_in"))
    )
    (net (code "85") (name "VUSB") (class "Default")
      (node (ref "J2-C") (pin "1") (pinfunction "VBUS_1") (pintype "power_in"))
      (node (ref "JP-CP") (pin "4") (pinfunction "4_4") (pintype "passive"))
    )
    (net (code "86") (name "WP") (class "Default")
      (node (ref "U0-C") (pin "115") (pinfunction "PD1_115") (pintype "bidirectional"))
      (node (ref "U1-C") (pin "3") (pinfunction "~{WP}/IO2_3") (pintype "bidirectional"))
    )
    (net (code "87") (name "unconnected-(JP-CS-Pad4)") (class "Default")
      (node (ref "JP-CS") (pin "4") (pinfunction "4_4") (pintype "passive"))
    )
    (net (code "88") (name "unconnected-(S0-0C-P1-Pad4)") (class "Default")
      (node (ref "S0-0C") (pin "4") (pinfunction "P1_4") (pintype "passive"))
    )
    (net (code "89") (name "unconnected-(S0-0C-S1-Pad2)") (class "Default")
      (node (ref "S0-0C") (pin "2") (pinfunction "S1_2") (pintype "passive"))
    )
    (net (code "90") (name "unconnected-(U0-C-PA4-Pad40)") (class "Default")
      (node (ref "U0-C") (pin "40") (pinfunction "PA4_40") (pintype "bidirectional"))
    )
    (net (code "91") (name "unconnected-(U0-C-PA9-Pad101)") (class "Default")
      (node (ref "U0-C") (pin "101") (pinfunction "PA9_101") (pintype "bidirectional"))
    )
    (net (code "92") (name "unconnected-(U0-C-PA15-Pad110)") (class "Default")
      (node (ref "U0-C") (pin "110") (pinfunction "PA15_110") (pintype "bidirectional"))
    )
    (net (code "93") (name "unconnected-(U0-C-PB2-Pad48)") (class "Default")
      (node (ref "U0-C") (pin "48") (pinfunction "PB2_48") (pintype "bidirectional"))
    )
    (net (code "94") (name "unconnected-(U0-C-PB4-Pad134)") (class "Default")
      (node (ref "U0-C") (pin "134") (pinfunction "PB4_134") (pintype "bidirectional"))
    )
    (net (code "95") (name "unconnected-(U0-C-PB5-Pad135)") (class "Default")
      (node (ref "U0-C") (pin "135") (pinfunction "PB5_135") (pintype "bidirectional"))
    )
    (net (code "96") (name "unconnected-(U0-C-PB6-Pad136)") (class "Default")
      (node (ref "U0-C") (pin "136") (pinfunction "PB6_136") (pintype "bidirectional"))
    )
    (net (code "97") (name "unconnected-(U0-C-PB7-Pad137)") (class "Default")
      (node (ref "U0-C") (pin "137") (pinfunction "PB7_137") (pintype "bidirectional"))
    )
    (net (code "98") (name "unconnected-(U0-C-PB8-Pad139)") (class "Default")
      (node (ref "U0-C") (pin "139") (pinfunction "PB8_139") (pintype "bidirectional"))
    )
    (net (code "99") (name "unconnected-(U0-C-PB9-Pad140)") (class "Default")
      (node (ref "U0-C") (pin "140") (pinfunction "PB9_140") (pintype "bidirectional"))
    )
    (net (code "100") (name "unconnected-(U0-C-PB12-Pad73)") (class "Default")
      (node (ref "U0-C") (pin "73") (pinfunction "PB12_73") (pintype "bidirectional"))
    )
    (net (code "101") (name "unconnected-(U0-C-PB13-Pad74)") (class "Default")
      (node (ref "U0-C") (pin "74") (pinfunction "PB13_74") (pintype "bidirectional"))
    )
    (net (code "102") (name "unconnected-(U0-C-PB14-Pad75)") (class "Default")
      (node (ref "U0-C") (pin "75") (pinfunction "PB14_75") (pintype "bidirectional"))
    )
    (net (code "103") (name "unconnected-(U0-C-PB15-Pad76)") (class "Default")
      (node (ref "U0-C") (pin "76") (pinfunction "PB15_76") (pintype "bidirectional"))
    )
    (net (code "104") (name "unconnected-(U0-C-PC0-Pad26)") (class "Default")
      (node (ref "U0-C") (pin "26") (pinfunction "PC0_26") (pintype "bidirectional"))
    )
    (net (code "105") (name "unconnected-(U0-C-PC1-Pad27)") (class "Default")
      (node (ref "U0-C") (pin "27") (pinfunction "PC1_27") (pintype "bidirectional"))
    )
    (net (code "106") (name "unconnected-(U0-C-PC2-Pad28)") (class "Default")
      (node (ref "U0-C") (pin "28") (pinfunction "PC2_28") (pintype "bidirectional"))
    )
    (net (code "107") (name "unconnected-(U0-C-PC3-Pad29)") (class "Default")
      (node (ref "U0-C") (pin "29") (pinfunction "PC3_29") (pintype "bidirectional"))
    )
    (net (code "108") (name "unconnected-(U0-C-PC13-Pad7)") (class "Default")
      (node (ref "U0-C") (pin "7") (pinfunction "PC13_7") (pintype "bidirectional"))
    )
    (net (code "109") (name "unconnected-(U0-C-PC14-Pad8)") (class "Default")
      (node (ref "U0-C") (pin "8") (pinfunction "PC14_8") (pintype "bidirectional"))
    )
    (net (code "110") (name "unconnected-(U0-C-PC15-Pad9)") (class "Default")
      (node (ref "U0-C") (pin "9") (pinfunction "PC15_9") (pintype "bidirectional"))
    )
    (net (code "111") (name "unconnected-(U0-C-PD3-Pad117)") (class "Default")
      (node (ref "U0-C") (pin "117") (pinfunction "PD3_117") (pintype "bidirectional"))
    )
    (net (code "112") (name "unconnected-(U0-C-PD4-Pad118)") (class "Default")
      (node (ref "U0-C") (pin "118") (pinfunction "PD4_118") (pintype "bidirectional"))
    )
    (net (code "113") (name "unconnected-(U0-C-PD5-Pad119)") (class "Default")
      (node (ref "U0-C") (pin "119") (pinfunction "PD5_119") (pintype "bidirectional"))
    )
    (net (code "114") (name "unconnected-(U0-C-PD6-Pad122)") (class "Default")
      (node (ref "U0-C") (pin "122") (pinfunction "PD6_122") (pintype "bidirectional"))
    )
    (net (code "115") (name "unconnected-(U0-C-PD7-Pad123)") (class "Default")
      (node (ref "U0-C") (pin "123") (pinfunction "PD7_123") (pintype "bidirectional"))
    )
    (net (code "116") (name "unconnected-(U0-C-PD8-Pad77)") (class "Default")
      (node (ref "U0-C") (pin "77") (pinfunction "PD8_77") (pintype "bidirectional"))
    )
    (net (code "117") (name "unconnected-(U0-C-PD9-Pad78)") (class "Default")
      (node (ref "U0-C") (pin "78") (pinfunction "PD9_78") (pintype "bidirectional"))
    )
    (net (code "118") (name "unconnected-(U0-C-PD10-Pad79)") (class "Default")
      (node (ref "U0-C") (pin "79") (pinfunction "PD10_79") (pintype "bidirectional"))
    )
    (net (code "119") (name "unconnected-(U0-C-PD11-Pad80)") (class "Default")
      (node (ref "U0-C") (pin "80") (pinfunction "PD11_80") (pintype "bidirectional"))
    )
    (net (code "120") (name "unconnected-(U0-C-PD12-Pad81)") (class "Default")
      (node (ref "U0-C") (pin "81") (pinfunction "PD12_81") (pintype "bidirectional"))
    )
    (net (code "121") (name "unconnected-(U0-C-PD13-Pad82)") (class "Default")
      (node (ref "U0-C") (pin "82") (pinfunction "PD13_82") (pintype "bidirectional"))
    )
    (net (code "122") (name "unconnected-(U0-C-PD14-Pad85)") (class "Default")
      (node (ref "U0-C") (pin "85") (pinfunction "PD14_85") (pintype "bidirectional"))
    )
    (net (code "123") (name "unconnected-(U0-C-PD15-Pad86)") (class "Default")
      (node (ref "U0-C") (pin "86") (pinfunction "PD15_86") (pintype "bidirectional"))
    )
    (net (code "124") (name "unconnected-(U0-C-PE0-Pad141)") (class "Default")
      (node (ref "U0-C") (pin "141") (pinfunction "PE0_141") (pintype "bidirectional"))
    )
    (net (code "125") (name "unconnected-(U0-C-PE1-Pad142)") (class "Default")
      (node (ref "U0-C") (pin "142") (pinfunction "PE1_142") (pintype "bidirectional"))
    )
    (net (code "126") (name "unconnected-(U0-C-PE3-Pad2)") (class "Default")
      (node (ref "U0-C") (pin "2") (pinfunction "PE3_2") (pintype "bidirectional"))
    )
    (net (code "127") (name "unconnected-(U0-C-PE4-Pad3)") (class "Default")
      (node (ref "U0-C") (pin "3") (pinfunction "PE4_3") (pintype "bidirectional"))
    )
    (net (code "128") (name "unconnected-(U0-C-PE5-Pad4)") (class "Default")
      (node (ref "U0-C") (pin "4") (pinfunction "PE5_4") (pintype "bidirectional"))
    )
    (net (code "129") (name "unconnected-(U0-C-PE6-Pad5)") (class "Default")
      (node (ref "U0-C") (pin "5") (pinfunction "PE6_5") (pintype "bidirectional"))
    )
    (net (code "130") (name "unconnected-(U0-C-PE9-Pad60)") (class "Default")
      (node (ref "U0-C") (pin "60") (pinfunction "PE9_60") (pintype "bidirectional"))
    )
    (net (code "131") (name "unconnected-(U0-C-PF0-Pad10)") (class "Default")
      (node (ref "U0-C") (pin "10") (pinfunction "PF0_10") (pintype "bidirectional"))
    )
    (net (code "132") (name "unconnected-(U0-C-PF5-Pad15)") (class "Default")
      (node (ref "U0-C") (pin "15") (pinfunction "PF5_15") (pintype "bidirectional"))
    )
    (net (code "133") (name "unconnected-(U0-C-PF10-Pad22)") (class "Default")
      (node (ref "U0-C") (pin "22") (pinfunction "PF10_22") (pintype "bidirectional"))
    )
    (net (code "134") (name "unconnected-(U0-C-PF11-Pad49)") (class "Default")
      (node (ref "U0-C") (pin "49") (pinfunction "PF11_49") (pintype "bidirectional"))
    )
    (net (code "135") (name "unconnected-(U0-C-PF12-Pad50)") (class "Default")
      (node (ref "U0-C") (pin "50") (pinfunction "PF12_50") (pintype "bidirectional"))
    )
    (net (code "136") (name "unconnected-(U0-C-PG2-Pad87)") (class "Default")
      (node (ref "U0-C") (pin "87") (pinfunction "PG2_87") (pintype "bidirectional"))
    )
    (net (code "137") (name "unconnected-(U0-C-PG3-Pad88)") (class "Default")
      (node (ref "U0-C") (pin "88") (pinfunction "PG3_88") (pintype "bidirectional"))
    )
    (net (code "138") (name "unconnected-(U0-C-PG5-Pad90)") (class "Default")
      (node (ref "U0-C") (pin "90") (pinfunction "PG5_90") (pintype "bidirectional"))
    )
    (net (code "139") (name "unconnected-(U0-C-PG6-Pad91)") (class "Default")
      (node (ref "U0-C") (pin "91") (pinfunction "PG6_91") (pintype "bidirectional"))
    )
    (net (code "140") (name "unconnected-(U0-C-PG7-Pad92)") (class "Default")
      (node (ref "U0-C") (pin "92") (pinfunction "PG7_92") (pintype "bidirectional"))
    )
    (net (code "141") (name "unconnected-(U0-C-PG8-Pad93)") (class "Default")
      (node (ref "U0-C") (pin "93") (pinfunction "PG8_93") (pintype "bidirectional"))
    )
    (net (code "142") (name "unconnected-(U0-C-PG9-Pad124)") (class "Default")
      (node (ref "U0-C") (pin "124") (pinfunction "PG9_124") (pintype "bidirectional"))
    )
    (net (code "143") (name "unconnected-(U0-C-PG10-Pad125)") (class "Default")
      (node (ref "U0-C") (pin "125") (pinfunction "PG10_125") (pintype "bidirectional"))
    )
    (net (code "144") (name "unconnected-(U0-C-PG11-Pad126)") (class "Default")
      (node (ref "U0-C") (pin "126") (pinfunction "PG11_126") (pintype "bidirectional"))
    )
    (net (code "145") (name "unconnected-(U0-C-PG12-Pad127)") (class "Default")
      (node (ref "U0-C") (pin "127") (pinfunction "PG12_127") (pintype "bidirectional"))
    )
    (net (code "146") (name "unconnected-(U0-C-PG13-Pad128)") (class "Default")
      (node (ref "U0-C") (pin "128") (pinfunction "PG13_128") (pintype "bidirectional"))
    )
    (net (code "147") (name "unconnected-(U0-C-PG14-Pad129)") (class "Default")
      (node (ref "U0-C") (pin "129") (pinfunction "PG14_129") (pintype "bidirectional"))
    )
    (net (code "148") (name "unconnected-(U0-C-PG15-Pad132)") (class "Default")
      (node (ref "U0-C") (pin "132") (pinfunction "PG15_132") (pintype "bidirectional"))
    )
    (net (code "149") (name "unconnected-(U1-C-EP-Pad9)") (class "Default")
      (node (ref "U1-C") (pin "9") (pinfunction "EP_9") (pintype "bidirectional"))
    )
  )
)
